# powermanage.net
KiCad netlist of a schematic drawn in Altium Designer
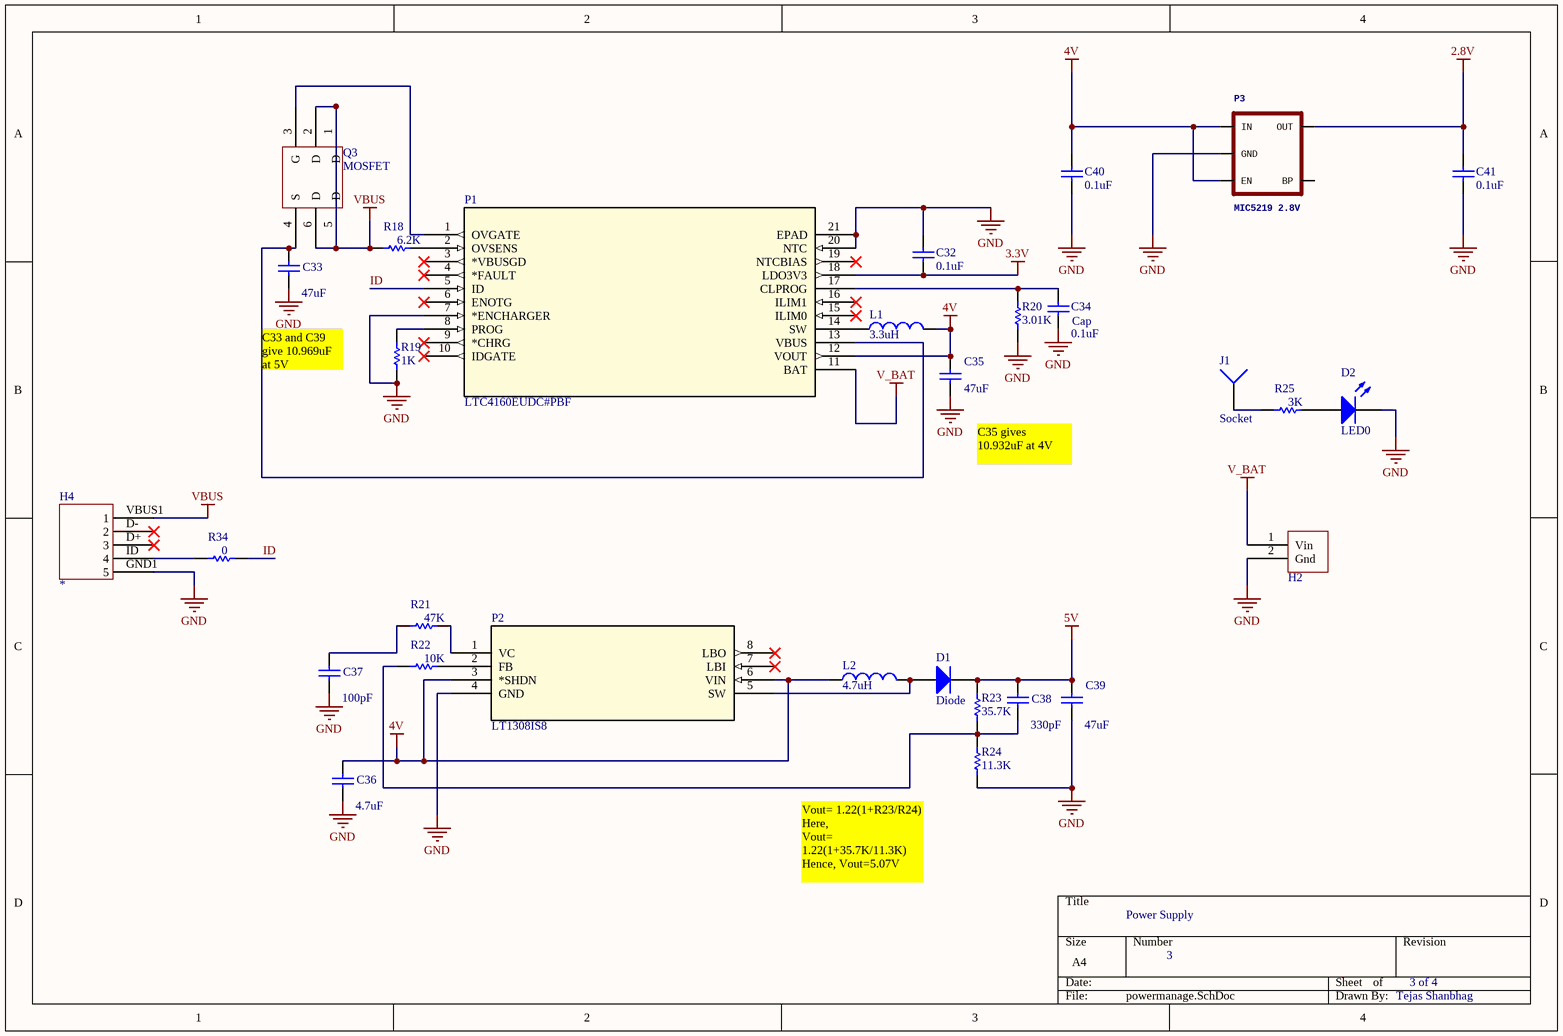
[diagram p0: powermanage.SchDoc]

(export (version "E")
  (design (tool "Eeschema 10.0.6"))
  (components
    (comp (ref "C32")
      (value "0.1uF")
      (footprint "1608[0603]")
      (description "CAP CER 0.1UF 10V X7R 0603")
      (fields (field (name "DIGIKEY PART NO") "399-1095-1-ND") (field (name "MANUFACTURER") "KEMET"))
      (libsource (lib "Miscellaneous Devices") (part "Cap Semi"))
    )
    (comp (ref "C33")
      (value "47uF")
      (footprint "6-0805_L")
      (description "CAP CER 47UF 6.3V X5R 0805")
      (fields
        (field (name "MANUFACTURER PART NUMBER") "GRM219R60J476ME44D")
        (field (name "DIGIKEY PART NO") "490-13249-1-ND")
      )
      (libsource (lib "Miscellaneous Devices") (part "Cap"))
    )
    (comp (ref "C34")
      (value "Cap")
      (footprint "1608[0603]")
      (description "CAP CER 0.1UF 16V X7R 0603")
      (fields
        (field (name "ALTIUM_VALUE") "0.1uF")
        (field (name "DIGIKEY PART NO") "311-1088-1-ND")
        (field (name "MANUFACTURER PART NUMBER") "CC0603KRX7R7BB104")
      )
      (libsource (lib "Miscellaneous Devices") (part "Cap"))
    )
    (comp (ref "C35")
      (value "47uF")
      (footprint "1608[0603]")
      (description "CAP CER 22UF 6.3V X5R 1206")
      (fields
        (field (name "MANUFACTURER PART NUMBER") "GRM188R60J476ME15D")
        (field (name "DIGIKEY PART NO") "490-13247-1-ND")
      )
      (libsource (lib "Miscellaneous Devices") (part "Cap"))
    )
    (comp (ref "C36")
      (value "4.7uF")
      (footprint "1608[0603]")
      (description "CAP CER 4.7UF 6.3V X7R 0603")
      (fields
        (field (name "MANUFACTURER PART NUMBER") "CL10B475KQ8NQNC")
        (field (name "DIGIKEY PART NO") "1276-2087-1-ND")
      )
      (libsource (lib "Miscellaneous Devices") (part "Cap"))
    )
    (comp (ref "C37")
      (value "100pF")
      (footprint "1608[0603]")
      (description "CAP CER 100PF 50V X7R 0603")
      (fields
        (field (name "MANUFACTURER PART NUMBER") "C0603C101K5RACTU")
        (field (name "DIGIKEY PART NO") "399-7824-1-ND")
      )
      (libsource (lib "Miscellaneous Devices") (part "Cap"))
    )
    (comp (ref "C38")
      (value "330pF")
      (footprint "1608[0603]")
      (description "CAP CER 330PF 100V X7R 0603")
      (fields
        (field (name "MANUFACTURER PART NUMBER") "CL10B331KC8WPNC")
        (field (name "DIGIKEY PART NO") "1276-6658-1-ND")
      )
      (libsource (lib "Miscellaneous Devices") (part "Cap"))
    )
    (comp (ref "C39")
      (value "47uF")
      (footprint "6-0805_L")
      (description "CAP CER 47UF 6.3V X5R 0805")
      (fields
        (field (name "MANUFACTURER PART NUMBER") "GRM219R60J476ME44D")
        (field (name "DIGIKEY PART NO") "490-13249-1-ND")
      )
      (libsource (lib "Miscellaneous Devices") (part "Cap"))
    )
    (comp (ref "C40")
      (value "0.1uF")
      (footprint "1608[0603]")
      (description "CAP CER 0.1UF 10V X7R 0603")
      (fields (field (name "DIGIKEY PART NO") "399-1095-1-ND") (field (name "MANUFACTURER") "KEMET"))
      (libsource (lib "Miscellaneous Devices") (part "Cap Semi"))
    )
    (comp (ref "C41")
      (value "0.1uF")
      (footprint "1608[0603]")
      (description "CAP CER 0.1UF 10V X7R 0603")
      (fields (field (name "DIGIKEY PART NO") "399-1095-1-ND") (field (name "MANUFACTURER") "KEMET"))
      (libsource (lib "Miscellaneous Devices") (part "Cap Semi"))
    )
    (comp (ref "D1")
      (value "Diode")
      (footprint "1608[0603]")
      (description "Default Diode")
      (fields
        (field (name "DIGIKEY PART NO") "CD0603-S01575CT-ND")
        (field (name "MANUFACTURER") "Bourns Inc.")
      )
      (libsource (lib "Miscellaneous Devices") (part "Diode"))
    )
    (comp (ref "D2")
      (value "LED0")
      (footprint "LED-0603")
      (description "Typical INFRARED GaAs LED")
      (fields
        (field (name "DIGIKEY PART NO") "732-4981-1-ND")
        (field (name "MANUFACTURER") "Wurth Electronics Inc.")
      )
      (libsource (lib "Miscellaneous Devices") (part "LED0"))
    )
    (comp (ref "H2")
      (value "Li-on")
      (footprint "battery")
      (fields
        (field (name "DIGIKEY PART NO") "455-1719-ND")
        (field (name "MANUFACTURER") "JST Sales America Inc.")
        (field (name "MANUFACTURER PART NUMBER") "S2B-PH-K-S(LF)(SN)")
      )
      (libsource (lib "parts") (part "battery"))
    )
    (comp (ref "H4")
      (value "*")
      (footprint "MicroUSB_ConnOld")
      (description "CONN RCPT USB MICRO AB SMD R/A")
      (fields
        (field (name "MANUFACTURER PART NUMBER") "ZX62-AB-5PA(31)")
        (field (name "MANUFACTURER") "Hirose Electric Co Ltd")
      )
      (libsource (lib "parts") (part "USB-AB-MICRO"))
    )
    (comp (ref "J1")
      (value "Socket")
      (footprint "PIN1")
      (fields (field (name "PUBLISHER") "Altium Limited"))
      (libsource (lib "Miscellaneous Connectors") (part "Socket"))
    )
    (comp (ref "L1")
      (value "3.3uH")
      (footprint "1608[0603]")
      (description "FIXED IND 3.3UH 30MA 1.3 OHM SMD")
      (fields (field (name "DIGIKEY PART NO") "587-1584-1-ND") (field (name "MANUFACTURER") "Taiyo Yuden"))
      (libsource (lib "Miscellaneous Devices") (part "Inductor"))
    )
    (comp (ref "L2")
      (value "4.7uH")
      (footprint "1608[0603]")
      (description "FIXED IND 4.7UH 350MA 500 MOHM")
      (fields
        (field (name "DIGIKEY PART NO") "445-6390-1-ND")
        (field (name "MANUFACTURER") "TDK Corporation")
      )
      (libsource (lib "Miscellaneous Devices") (part "Inductor"))
    )
    (comp (ref "P1")
      (value "LTC4160EUDC#PBF")
      (footprint "LTC4160")
      (description "IC SWITCH POWER MANAGER 20-QFN")
      (fields
        (field (name "DIGIKEY PART NO") "TC4160EUDC#PBF-ND")
        (field (name "MANUFACTURER") "Linear Technology")
      )
      (libsource (lib "2017-02-28_19-25-41") (part "LTC4160EUDC#PBF"))
    )
    (comp (ref "P2")
      (value "LT1308IS8")
      (footprint "LTC1308")
      (description "IC REG BOOST ADJ 2A 8SOIC")
      (fields
        (field (name "MANUFACTURER PART NUMBER") "LT1308IS8#PBF")
        (field (name "MANUFACTURER") "Linear Technology")
      )
      (libsource (lib "LPEDT_Parts") (part "LT1308IS8"))
    )
    (comp (ref "P3")
      (value "MIC5219 2.8V")
      (footprint "SOT23-5")
      (fields
        (field (name "MANUFACTURER PART NUMBER") "MIC5219-2.8YM5-TR")
        (field (name "MANUFACTURER") "Microchip Technology")
        (field (name "DIGIKEY PART NO") "576-2762-1-ND")
      )
      (libsource (lib "Correll_sensor_parts") (part "V_REG_MIC52193.3V"))
    )
    (comp (ref "Q3")
      (value "MOSFET")
      (footprint "MOSFET SI3442")
      (description "MOSFET N-CH 20V 3A 6-TSOP")
      (fields
        (field (name "DIGIKEY PART NO") "SI3442BDV-T1-E3CT-ND")
        (field (name "MANUFACTURER PART NUMBER") "SI3442BDV-T1-E3")
      )
      (libsource (lib "parts") (part "MOSFET"))
    )
    (comp (ref "R18")
      (value "6.2K")
      (footprint "1608[0603]")
      (description "RES SMD 6.2K OHM 1% 1/10W 0603")
      (fields (field (name "DIGIKEY PART NO") "311-6.20KHRCT-ND") (field (name "MANUFACTURER") "Yageo"))
      (libsource (lib "Miscellaneous Devices") (part "Res1"))
    )
    (comp (ref "R19")
      (value "1K")
      (footprint "1608[0603]")
      (description "RES SMD 1K OHM 1% 1/10W 0603")
      (fields (field (name "DIGIKEY PART NO") "311-1.00KHRCT-ND") (field (name "MANUFACTURER") "Yageo"))
      (libsource (lib "Miscellaneous Devices") (part "Res1"))
    )
    (comp (ref "R20")
      (value "3.01K")
      (footprint "1608[0603]")
      (description "RES SMD 3.01K OHM 1% 1/10W 0603")
      (fields (field (name "DIGIKEY PART NO") "311-3.01KHRCT-ND") (field (name "MANUFACTURER") "Yageo"))
      (libsource (lib "Miscellaneous Devices") (part "Res1"))
    )
    (comp (ref "R21")
      (value "47K")
      (footprint "1608[0603]")
      (description "RES SMD 47K OHM 1% 1/10W 0603")
      (fields (field (name "DIGIKEY PART NO") "311-47.0KHRCT-ND") (field (name "MANUFACTURER") "Yageo"))
      (libsource (lib "Miscellaneous Devices") (part "Res1"))
    )
    (comp (ref "R22")
      (value "10K")
      (footprint "1608[0603]")
      (description "RES SMD 10K OHM 1% 1/10W 0603")
      (fields (field (name "DIGIKEY PART NO") "311-10.0KHRCT-ND") (field (name "MANUFACTURER") "Yageo"))
      (libsource (lib "Miscellaneous Devices") (part "Res1"))
    )
    (comp (ref "R23")
      (value "35.7K")
      (footprint "1608[0603]")
      (description "RES SMD 35.7K OHM 1% 1/10W 0603")
      (fields (field (name "DIGIKEY PART NO") "311-35.7KHRCT-ND") (field (name "MANUFACTURER") "Yageo"))
      (libsource (lib "Miscellaneous Devices") (part "Res1"))
    )
    (comp (ref "R24")
      (value "11.3K")
      (footprint "1608[0603]")
      (description "RES SMD 11.3K OHM 1% 1/10W 0603")
      (fields (field (name "DIGIKEY PART NO") "311-11.3KHRCT-ND") (field (name "MANUFACTURER") "Yageo"))
      (libsource (lib "Miscellaneous Devices") (part "Res1"))
    )
    (comp (ref "R25")
      (value "3K")
      (footprint "1608[0603]")
      (description "RES SMD 10K OHM 1% 1/10W 0603")
      (fields (field (name "DIGIKEY PART NO") "311-10.0KHRCT-ND") (field (name "MANUFACTURER") "Yageo"))
      (libsource (lib "Miscellaneous Devices") (part "Res1"))
    )
    (comp (ref "R34")
      (value "0")
      (footprint "1608[0603]")
      (description "RES SMD 47K OHM 1% 1/10W 0603")
      (fields (field (name "DIGIKEY PART NO") "311-47.0KHRCT-ND") (field (name "MANUFACTURER") "Yageo"))
      (libsource (lib "Miscellaneous Devices") (part "Res1"))
    )
  )
  (nets
    (net (code "1") (name "/ID") (class "Default")
      (node (ref "P1") (pin "5") (pinfunction "ID_5") (pintype "input"))
      (node (ref "R34") (pin "2") (pinfunction "2_2") (pintype "passive"))
    )
    (net (code "2") (name "2.8V") (class "Default")
      (node (ref "C41") (pin "2") (pinfunction "2_2") (pintype "passive"))
      (node (ref "P3") (pin "5") (pinfunction "OUT_5") (pintype "passive"))
    )
    (net (code "3") (name "3.3V") (class "Default")
      (node (ref "C32") (pin "1") (pinfunction "1_1") (pintype "passive"))
      (node (ref "P1") (pin "18") (pinfunction "LDO3V3_18") (pintype "output"))
    )
    (net (code "4") (name "4V") (class "Default")
      (node (ref "C35") (pin "2") (pinfunction "2_2") (pintype "passive"))
      (node (ref "C36") (pin "2") (pinfunction "2_2") (pintype "passive"))
      (node (ref "C40") (pin "2") (pinfunction "2_2") (pintype "passive"))
      (node (ref "L1") (pin "2") (pinfunction "2_2") (pintype "passive"))
      (node (ref "L2") (pin "1") (pinfunction "1_1") (pintype "passive"))
      (node (ref "P1") (pin "12") (pinfunction "VOUT_12") (pintype "output"))
      (node (ref "P2") (pin "3") (pinfunction "*SHDN_3") (pintype "passive"))
      (node (ref "P2") (pin "6") (pinfunction "VIN_6") (pintype "input"))
      (node (ref "P3") (pin "1") (pinfunction "IN_1") (pintype "passive"))
      (node (ref "P3") (pin "3") (pinfunction "EN_3") (pintype "passive"))
    )
    (net (code "5") (name "5V") (class "Default")
      (node (ref "C38") (pin "2") (pinfunction "2_2") (pintype "passive"))
      (node (ref "C39") (pin "2") (pinfunction "2_2") (pintype "passive"))
      (node (ref "D1") (pin "2") (pinfunction "K_2") (pintype "passive"))
      (node (ref "R23") (pin "2") (pinfunction "2_2") (pintype "passive"))
    )
    (net (code "6") (name "GND") (class "Default")
      (node (ref "C32") (pin "2") (pinfunction "2_2") (pintype "passive"))
      (node (ref "C33") (pin "1") (pinfunction "1_1") (pintype "passive"))
      (node (ref "C34") (pin "2") (pinfunction "2_2") (pintype "passive"))
      (node (ref "C35") (pin "1") (pinfunction "1_1") (pintype "passive"))
      (node (ref "C36") (pin "1") (pinfunction "1_1") (pintype "passive"))
      (node (ref "C37") (pin "1") (pinfunction "1_1") (pintype "passive"))
      (node (ref "C39") (pin "1") (pinfunction "1_1") (pintype "passive"))
      (node (ref "C40") (pin "1") (pinfunction "1_1") (pintype "passive"))
      (node (ref "C41") (pin "1") (pinfunction "1_1") (pintype "passive"))
      (node (ref "D2") (pin "2") (pinfunction "K_2") (pintype "passive"))
      (node (ref "H2") (pin "2") (pinfunction "Gnd_2") (pintype "power_in"))
      (node (ref "H4") (pin "GND1") (pinfunction "5_GND1") (pintype "passive"))
      (node (ref "P1") (pin "20") (pinfunction "NTC_20") (pintype "input"))
      (node (ref "P1") (pin "21") (pinfunction "EPAD_21") (pintype "passive"))
      (node (ref "P1") (pin "7") (pinfunction "*ENCHARGER_7") (pintype "input"))
      (node (ref "P2") (pin "4") (pinfunction "GND_4") (pintype "power_in"))
      (node (ref "P3") (pin "2") (pinfunction "GND_2") (pintype "passive"))
      (node (ref "R19") (pin "1") (pinfunction "1_1") (pintype "passive"))
      (node (ref "R20") (pin "2") (pinfunction "2_2") (pintype "passive"))
      (node (ref "R24") (pin "1") (pinfunction "1_1") (pintype "passive"))
    )
    (net (code "7") (name "Net-(C37-Pad2)") (class "Default")
      (node (ref "C37") (pin "2") (pinfunction "2_2") (pintype "passive"))
      (node (ref "R21") (pin "1") (pinfunction "1_1") (pintype "passive"))
    )
    (net (code "8") (name "Net-(C38-Pad1)") (class "Default")
      (node (ref "C38") (pin "1") (pinfunction "1_1") (pintype "passive"))
      (node (ref "R22") (pin "1") (pinfunction "1_1") (pintype "passive"))
      (node (ref "R23") (pin "1") (pinfunction "1_1") (pintype "passive"))
      (node (ref "R24") (pin "2") (pinfunction "2_2") (pintype "passive"))
    )
    (net (code "9") (name "Net-(D1-A)") (class "Default")
      (node (ref "D1") (pin "1") (pinfunction "A_1") (pintype "passive"))
      (node (ref "L2") (pin "2") (pinfunction "2_2") (pintype "passive"))
      (node (ref "P2") (pin "5") (pinfunction "SW_5") (pintype "passive"))
    )
    (net (code "10") (name "Net-(D2-A)") (class "Default")
      (node (ref "D2") (pin "1") (pinfunction "A_1") (pintype "passive"))
      (node (ref "R25") (pin "2") (pinfunction "2_2") (pintype "passive"))
    )
    (net (code "11") (name "Net-(H4-4)") (class "Default")
      (node (ref "H4") (pin "ID") (pinfunction "4_ID") (pintype "passive"))
      (node (ref "R34") (pin "1") (pinfunction "1_1") (pintype "passive"))
    )
    (net (code "12") (name "Net-(J1-Pad1)") (class "Default")
      (node (ref "J1") (pin "1") (pinfunction "1_1") (pintype "passive"))
      (node (ref "R25") (pin "1") (pinfunction "1_1") (pintype "passive"))
    )
    (net (code "13") (name "Net-(P1-CLPROG)") (class "Default")
      (node (ref "C34") (pin "1") (pinfunction "1_1") (pintype "passive"))
      (node (ref "P1") (pin "17") (pinfunction "CLPROG_17") (pintype "passive"))
      (node (ref "R20") (pin "1") (pinfunction "1_1") (pintype "passive"))
    )
    (net (code "14") (name "Net-(P1-OVGATE)") (class "Default")
      (node (ref "P1") (pin "1") (pinfunction "OVGATE_1") (pintype "output"))
      (node (ref "Q3") (pin "3") (pinfunction "G_3") (pintype "passive"))
    )
    (net (code "15") (name "Net-(P1-OVSENS)") (class "Default")
      (node (ref "P1") (pin "2") (pinfunction "OVSENS_2") (pintype "input"))
      (node (ref "R18") (pin "2") (pinfunction "2_2") (pintype "passive"))
    )
    (net (code "16") (name "Net-(P1-PROG)") (class "Default")
      (node (ref "P1") (pin "8") (pinfunction "PROG_8") (pintype "input"))
      (node (ref "R19") (pin "2") (pinfunction "2_2") (pintype "passive"))
    )
    (net (code "17") (name "Net-(P1-SW)") (class "Default")
      (node (ref "L1") (pin "1") (pinfunction "1_1") (pintype "passive"))
      (node (ref "P1") (pin "14") (pinfunction "SW_14") (pintype "passive"))
    )
    (net (code "18") (name "Net-(P1-VBUS)") (class "Default")
      (node (ref "C33") (pin "2") (pinfunction "2_2") (pintype "passive"))
      (node (ref "P1") (pin "13") (pinfunction "VBUS_13") (pintype "passive"))
      (node (ref "Q3") (pin "4") (pinfunction "S_4") (pintype "passive"))
    )
    (net (code "19") (name "Net-(P2-FB)") (class "Default")
      (node (ref "P2") (pin "2") (pinfunction "FB_2") (pintype "passive"))
      (node (ref "R22") (pin "2") (pinfunction "2_2") (pintype "passive"))
    )
    (net (code "20") (name "Net-(P2-VC)") (class "Default")
      (node (ref "P2") (pin "1") (pinfunction "VC_1") (pintype "passive"))
      (node (ref "R21") (pin "2") (pinfunction "2_2") (pintype "passive"))
    )
    (net (code "21") (name "VBUS") (class "Default")
      (node (ref "H4") (pin "VBUS1") (pinfunction "1_VBUS1") (pintype "passive"))
      (node (ref "Q3") (pin "1") (pinfunction "D_1") (pintype "passive"))
      (node (ref "Q3") (pin "2") (pinfunction "D_2") (pintype "passive"))
      (node (ref "Q3") (pin "5") (pinfunction "D_5") (pintype "passive"))
      (node (ref "Q3") (pin "6") (pinfunction "D_6") (pintype "passive"))
      (node (ref "R18") (pin "1") (pinfunction "1_1") (pintype "passive"))
    )
    (net (code "22") (name "V_BAT") (class "Default")
      (node (ref "H2") (pin "1") (pinfunction "Vin_1") (pintype "power_in"))
      (node (ref "P1") (pin "11") (pinfunction "BAT_11") (pintype "passive"))
    )
    (net (code "23") (name "unconnected-(H4-2-PadD-)") (class "Default")
      (node (ref "H4") (pin "D-") (pinfunction "2_D-") (pintype "passive+no_connect"))
    )
    (net (code "24") (name "unconnected-(H4-3-PadD+)") (class "Default")
      (node (ref "H4") (pin "D+") (pinfunction "3_D+") (pintype "passive+no_connect"))
    )
    (net (code "25") (name "unconnected-(P1-*CHRG-Pad9)") (class "Default")
      (node (ref "P1") (pin "9") (pinfunction "*CHRG_9") (pintype "output+no_connect"))
    )
    (net (code "26") (name "unconnected-(P1-*FAULT-Pad4)") (class "Default")
      (node (ref "P1") (pin "4") (pinfunction "*FAULT_4") (pintype "output+no_connect"))
    )
    (net (code "27") (name "unconnected-(P1-*VBUSGD-Pad3)") (class "Default")
      (node (ref "P1") (pin "3") (pinfunction "*VBUSGD_3") (pintype "output+no_connect"))
    )
    (net (code "28") (name "unconnected-(P1-ENOTG-Pad6)") (class "Default")
      (node (ref "P1") (pin "6") (pinfunction "ENOTG_6") (pintype "input+no_connect"))
    )
    (net (code "29") (name "unconnected-(P1-IDGATE-Pad10)") (class "Default")
      (node (ref "P1") (pin "10") (pinfunction "IDGATE_10") (pintype "output+no_connect"))
    )
    (net (code "30") (name "unconnected-(P1-ILIM0-Pad15)") (class "Default")
      (node (ref "P1") (pin "15") (pinfunction "ILIM0_15") (pintype "input+no_connect"))
    )
    (net (code "31") (name "unconnected-(P1-ILIM1-Pad16)") (class "Default")
      (node (ref "P1") (pin "16") (pinfunction "ILIM1_16") (pintype "input+no_connect"))
    )
    (net (code "32") (name "unconnected-(P1-NTCBIAS-Pad19)") (class "Default")
      (node (ref "P1") (pin "19") (pinfunction "NTCBIAS_19") (pintype "output+no_connect"))
    )
    (net (code "33") (name "unconnected-(P2-LBI-Pad7)") (class "Default")
      (node (ref "P2") (pin "7") (pinfunction "LBI_7") (pintype "input+no_connect"))
    )
    (net (code "34") (name "unconnected-(P2-LBO-Pad8)") (class "Default")
      (node (ref "P2") (pin "8") (pinfunction "LBO_8") (pintype "output+no_connect"))
    )
    (net (code "35") (name "unconnected-(P3-BP-Pad4)") (class "Default")
      (node (ref "P3") (pin "4") (pinfunction "BP_4") (pintype "passive"))
    )
  )
)
